# DriverModule.net
KiCad netlist of a schematic drawn in Altium Designer
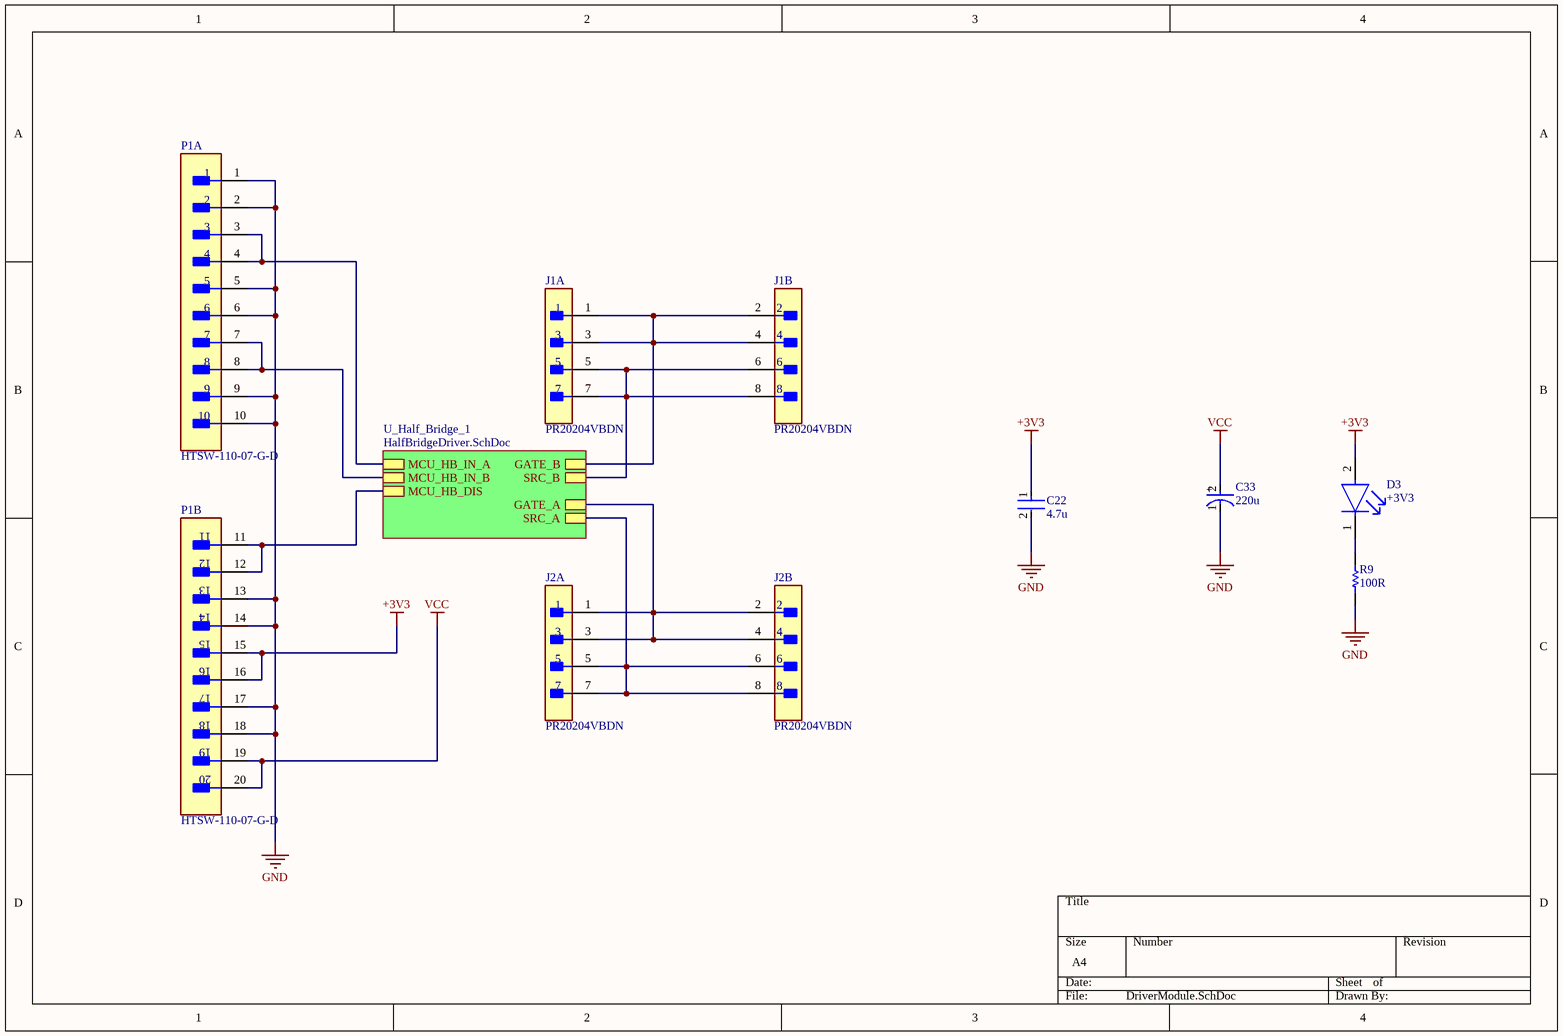
[diagram p0: DriverModule.SchDoc]

(export (version "E")
  (design (tool "Eeschema 10.0.6"))
  (components
    (comp (ref "C22")
      (value "4.7u")
      (footprint "FP-GRM31C-0_2-e0_3_0_8-IPC_C")
      (description "Chip Multilayer Ceramic Capacitors for General Purpose, 1206, 4.7uF, X7R, 15%, 20%, 50V")
      (fields (field (name "TOLERANCE") "20%"))
      (libsource (lib "Altium Content Vault") (part "02cd4be3c70576c341d710602a673aa"))
    )
    (comp (ref "C33")
      (value "220u")
      (footprint "FP-RAD-TH-D_5_0_5-L_7_1-F-MFG")
      (description "Aluminum Electrolytic Capacitors (Radial Lead Type) 22uF ±20% 25V")
      (fields (field (name "TOLERANCE") "20%"))
      (libsource (lib "Altium Content Vault") (part "a00bbbee19879c290e62620ae7e47b1"))
    )
    (comp (ref "D3")
      (value "+3V3")
      (footprint "FP-LTST-C171KGKT-MFG")
      (description "LED GREEN CLEAR SMD")
      (libsource (lib "Altium Content Vault") (part "8706943c75ba83719d021d2fdc84c58"))
    )
    (comp (ref "J1")
      (value "PR20204VBDN")
      (footprint "FP-PR20204VBDN-MFG")
      (description "PIN HEADER, THR, DUAL ROW, .100\"")
      (libsource (lib "") (part "811e954b9c034aa737de4d9295cbe7e_1"))
    )
    (comp (ref "J2")
      (value "PR20204VBDN")
      (footprint "FP-PR20204VBDN-MFG")
      (description "PIN HEADER, THR, DUAL ROW, .100\"")
      (libsource (lib "") (part "811e954b9c034aa737de4d9295cbe7e_1"))
    )
    (comp (ref "P1")
      (value "HTSW-110-07-G-D")
      (footprint "FP-HTSW-110-07-G-D-MFG")
      (description "CONN HEADER VERT 20POS 2.54MM")
      (libsource (lib "Altium Content Vault") (part "00b7ec758158f2d3e337df3b55160e4"))
    )
    (comp (ref "R9")
      (value "100R")
      (footprint "RESC2013X60X35ML10T20")
      (description "Chip Resistor, 100 Ohm, +/-1%, 0.125 W, -55 to 155 degC, 0805 (2012 Metric), RoHS, Tape and Reel")
      (fields (field (name "TOLERANCE") "1%") (field (name "MANUFACTURER") "Yageo"))
      (libsource (lib "Altium Content Vault") (part "RES-2"))
    )
  )
  (nets
    (net (code "1") (name "+3V3") (class "Default")
      (node (ref "C22") (pin "1") (pinfunction "1_1") (pintype "passive"))
      (node (ref "D3") (pin "2") (pinfunction "A_2") (pintype "passive"))
      (node (ref "P1") (pin "15") (pinfunction "15_15") (pintype "passive"))
      (node (ref "P1") (pin "16") (pinfunction "16_16") (pintype "passive"))
    )
    (net (code "2") (name "/GATE_A") (class "Default")
      (node (ref "J2") (pin "1") (pinfunction "1_1") (pintype "passive"))
      (node (ref "J2") (pin "2") (pinfunction "2_2") (pintype "passive"))
      (node (ref "J2") (pin "3") (pinfunction "3_3") (pintype "passive"))
      (node (ref "J2") (pin "4") (pinfunction "4_4") (pintype "passive"))
    )
    (net (code "3") (name "/GATE_B") (class "Default")
      (node (ref "J1") (pin "1") (pinfunction "1_1") (pintype "passive"))
      (node (ref "J1") (pin "2") (pinfunction "2_2") (pintype "passive"))
      (node (ref "J1") (pin "3") (pinfunction "3_3") (pintype "passive"))
      (node (ref "J1") (pin "4") (pinfunction "4_4") (pintype "passive"))
    )
    (net (code "4") (name "/MCU_HB_DIS") (class "Default")
      (node (ref "P1") (pin "11") (pinfunction "11_11") (pintype "passive"))
      (node (ref "P1") (pin "12") (pinfunction "12_12") (pintype "passive"))
    )
    (net (code "5") (name "/MCU_HB_IN_A") (class "Default")
      (node (ref "P1") (pin "3") (pinfunction "3_3") (pintype "passive"))
      (node (ref "P1") (pin "4") (pinfunction "4_4") (pintype "passive"))
    )
    (net (code "6") (name "/MCU_HB_IN_B") (class "Default")
      (node (ref "P1") (pin "7") (pinfunction "7_7") (pintype "passive"))
      (node (ref "P1") (pin "8") (pinfunction "8_8") (pintype "passive"))
    )
    (net (code "7") (name "/SRC_A") (class "Default")
      (node (ref "J2") (pin "5") (pinfunction "5_5") (pintype "passive"))
      (node (ref "J2") (pin "6") (pinfunction "6_6") (pintype "passive"))
      (node (ref "J2") (pin "7") (pinfunction "7_7") (pintype "passive"))
      (node (ref "J2") (pin "8") (pinfunction "8_8") (pintype "passive"))
    )
    (net (code "8") (name "/SRC_B") (class "Default")
      (node (ref "J1") (pin "5") (pinfunction "5_5") (pintype "passive"))
      (node (ref "J1") (pin "6") (pinfunction "6_6") (pintype "passive"))
      (node (ref "J1") (pin "7") (pinfunction "7_7") (pintype "passive"))
      (node (ref "J1") (pin "8") (pinfunction "8_8") (pintype "passive"))
    )
    (net (code "9") (name "GND") (class "Default")
      (node (ref "C22") (pin "2") (pinfunction "2_2") (pintype "passive"))
      (node (ref "C33") (pin "1") (pinfunction "C_1") (pintype "passive"))
      (node (ref "P1") (pin "1") (pinfunction "1_1") (pintype "passive"))
      (node (ref "P1") (pin "10") (pinfunction "10_10") (pintype "passive"))
      (node (ref "P1") (pin "13") (pinfunction "13_13") (pintype "passive"))
      (node (ref "P1") (pin "14") (pinfunction "14_14") (pintype "passive"))
      (node (ref "P1") (pin "17") (pinfunction "17_17") (pintype "passive"))
      (node (ref "P1") (pin "18") (pinfunction "18_18") (pintype "passive"))
      (node (ref "P1") (pin "2") (pinfunction "2_2") (pintype "passive"))
      (node (ref "P1") (pin "5") (pinfunction "5_5") (pintype "passive"))
      (node (ref "P1") (pin "6") (pinfunction "6_6") (pintype "passive"))
      (node (ref "P1") (pin "9") (pinfunction "9_9") (pintype "passive"))
      (node (ref "R9") (pin "1") (pinfunction "1_1") (pintype "passive"))
    )
    (net (code "10") (name "Net-(D3-C)") (class "Default")
      (node (ref "D3") (pin "1") (pinfunction "C_1") (pintype "passive"))
      (node (ref "R9") (pin "2") (pinfunction "2_2") (pintype "passive"))
    )
    (net (code "11") (name "VCC") (class "Default")
      (node (ref "C33") (pin "2") (pinfunction "A_2") (pintype "passive"))
      (node (ref "P1") (pin "19") (pinfunction "19_19") (pintype "passive"))
      (node (ref "P1") (pin "20") (pinfunction "20_20") (pintype "passive"))
    )
  )
)
